# RPI_SmartServo_th_v2.net
KiCad netlist of a schematic drawn in EAGLE
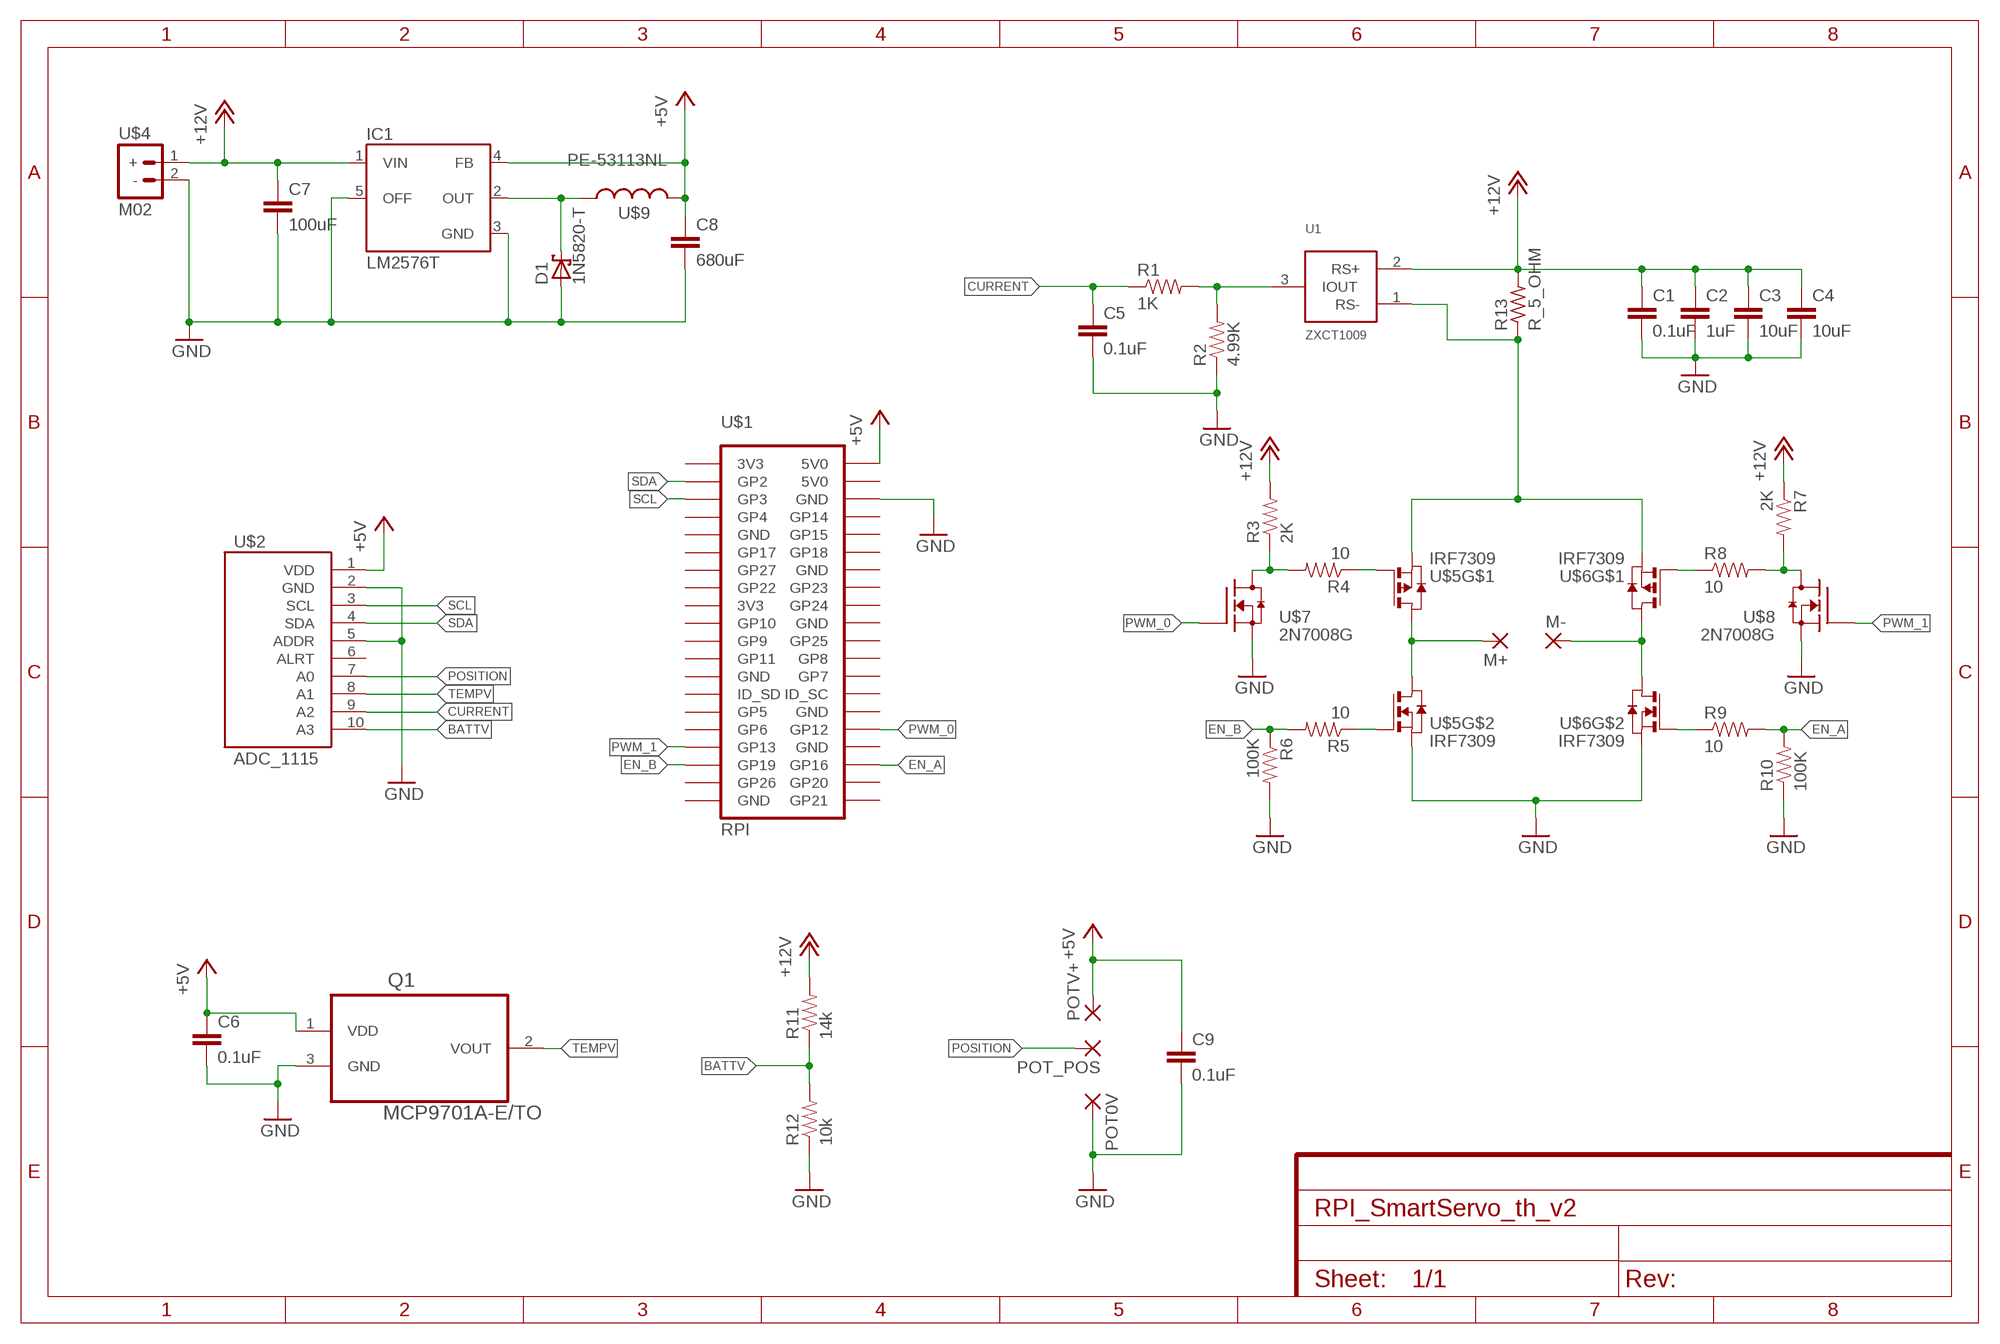
[diagram p0: schematic, sheet 1]

(export (version "E")
  (design (tool "Eeschema 10.0.6"))
  (components
    (comp (ref "C1")
      (value "0.1uF")
      (footprint "eagle-import:C025-025X050")
      (libsource (lib "eagle-import") (part "C-EU025-025X050"))
    )
    (comp (ref "C2")
      (value "1uF")
      (footprint "eagle-import:C025-025X050")
      (libsource (lib "eagle-import") (part "C-EU025-025X050"))
    )
    (comp (ref "C3")
      (value "10uF")
      (footprint "eagle-import:C025-025X050")
      (libsource (lib "eagle-import") (part "C-EU025-025X050"))
    )
    (comp (ref "C4")
      (value "10uF")
      (footprint "eagle-import:C025-025X050")
      (libsource (lib "eagle-import") (part "C-EU025-025X050"))
    )
    (comp (ref "C5")
      (value "0.1uF")
      (footprint "eagle-import:C025-025X050")
      (libsource (lib "eagle-import") (part "C-EU025-025X050"))
    )
    (comp (ref "C6")
      (value "0.1uF")
      (footprint "eagle-import:C025-025X050")
      (libsource (lib "eagle-import") (part "C-EU025-025X050"))
    )
    (comp (ref "C7")
      (value "100uF")
      (footprint "eagle-import:C025-025X050")
      (libsource (lib "eagle-import") (part "C-EU025-025X050"))
    )
    (comp (ref "C8")
      (value "680uF")
      (footprint "eagle-import:C025-025X050")
      (libsource (lib "eagle-import") (part "C-EU025-025X050"))
    )
    (comp (ref "C9")
      (value "0.1uF")
      (footprint "eagle-import:C025-025X050")
      (libsource (lib "eagle-import") (part "C-EU025-025X050"))
    )
    (comp (ref "D1")
      (value "1N5820-T")
      (footprint "eagle-import:C4111-15")
      (libsource (lib "eagle-import") (part "SCHOTTKY-DIODEC4111-15"))
    )
    (comp (ref "IC1")
      (value "LM2576T")
      (footprint "eagle-import:TO220-5")
      (libsource (lib "eagle-import") (part "LM2576T"))
    )
    (comp (ref "M+")
      (value "1,6/0,9")
      (footprint "eagle-import:1,6_0,9")
      (libsource (lib "eagle-import") (part "1,6/0,9"))
    )
    (comp (ref "M-")
      (value "1,6/0,9")
      (footprint "eagle-import:1,6_0,9")
      (libsource (lib "eagle-import") (part "1,6/0,9"))
    )
    (comp (ref "POT0V")
      (value "1,6/0,9")
      (footprint "eagle-import:1,6_0,9")
      (libsource (lib "eagle-import") (part "1,6/0,9"))
    )
    (comp (ref "POTV+")
      (value "1,6/0,9")
      (footprint "eagle-import:1,6_0,9")
      (libsource (lib "eagle-import") (part "1,6/0,9"))
    )
    (comp (ref "POT_POS")
      (value "1,6/0,9")
      (footprint "eagle-import:1,6_0,9")
      (libsource (lib "eagle-import") (part "1,6/0,9"))
    )
    (comp (ref "Q1")
      (value "MCP9701A-E/TO")
      (footprint "eagle-import:TO127P254X533-3")
      (libsource (lib "eagle-import") (part "MCP9701A-E/TO"))
    )
    (comp (ref "R1")
      (value "1K")
      (footprint "eagle-import:AXIAL-0.4")
      (libsource (lib "eagle-import") (part "RESISTORPTH-1/4W"))
    )
    (comp (ref "R2")
      (value "4.99K")
      (footprint "eagle-import:AXIAL-0.4")
      (libsource (lib "eagle-import") (part "RESISTORPTH-1/4W"))
    )
    (comp (ref "R3")
      (value "2K")
      (footprint "eagle-import:AXIAL-0.4")
      (libsource (lib "eagle-import") (part "RESISTORPTH-1/4W"))
    )
    (comp (ref "R4")
      (value "10")
      (footprint "eagle-import:AXIAL-0.4")
      (libsource (lib "eagle-import") (part "RESISTORPTH-1/4W"))
    )
    (comp (ref "R5")
      (value "10")
      (footprint "eagle-import:AXIAL-0.4")
      (libsource (lib "eagle-import") (part "RESISTORPTH-1/4W"))
    )
    (comp (ref "R6")
      (value "100K")
      (footprint "eagle-import:AXIAL-0.4")
      (libsource (lib "eagle-import") (part "RESISTORPTH-1/4W"))
    )
    (comp (ref "R7")
      (value "2K")
      (footprint "eagle-import:AXIAL-0.4")
      (libsource (lib "eagle-import") (part "RESISTORPTH-1/4W"))
    )
    (comp (ref "R8")
      (value "10")
      (footprint "eagle-import:AXIAL-0.4")
      (libsource (lib "eagle-import") (part "RESISTORPTH-1/4W"))
    )
    (comp (ref "R9")
      (value "10")
      (footprint "eagle-import:AXIAL-0.4")
      (libsource (lib "eagle-import") (part "RESISTORPTH-1/4W"))
    )
    (comp (ref "R10")
      (value "100K")
      (footprint "eagle-import:AXIAL-0.4")
      (libsource (lib "eagle-import") (part "RESISTORPTH-1/4W"))
    )
    (comp (ref "R11")
      (value "14k")
      (footprint "eagle-import:AXIAL-0.4")
      (libsource (lib "eagle-import") (part "RESISTORPTH-1/4W"))
    )
    (comp (ref "R12")
      (value "10k")
      (footprint "eagle-import:AXIAL-0.4")
      (libsource (lib "eagle-import") (part "RESISTORPTH-1/4W"))
    )
    (comp (ref "R13")
      (value "R_5_OHM")
      (footprint "eagle-import:0922_22")
      (libsource (lib "eagle-import") (part "R_5_OHM"))
    )
    (comp (ref "U$1")
      (value "RPI")
      (footprint "eagle-import:2X20")
      (libsource (lib "eagle-import") (part "RPI"))
    )
    (comp (ref "U$2")
      (value "ADC_1115")
      (footprint "eagle-import:1X10")
      (libsource (lib "eagle-import") (part "ADC_1115"))
    )
    (comp (ref "U$4")
      (value "M02")
      (footprint "eagle-import:1X02")
      (libsource (lib "eagle-import") (part "M02"))
    )
    (comp (ref "U$5")
      (value "IRF7309")
      (footprint "eagle-import:SO8")
      (libsource (lib "eagle-import") (part "IRF7309"))
    )
    (comp (ref "U$6")
      (value "IRF7309")
      (footprint "eagle-import:SO8")
      (libsource (lib "eagle-import") (part "IRF7309"))
    )
    (comp (ref "U$7")
      (value "2N7008G")
      (footprint "eagle-import:TO-92")
      (libsource (lib "eagle-import") (part "2N7008G"))
    )
    (comp (ref "U$8")
      (value "2N7008G")
      (footprint "eagle-import:TO-92")
      (libsource (lib "eagle-import") (part "2N7008G"))
    )
    (comp (ref "U$9")
      (value "PE-53113NL")
      (footprint "eagle-import:KM-4")
      (libsource (lib "eagle-import") (part "PE-53113NL"))
    )
    (comp (ref "U1")
      (value "ZXCT1009")
      (footprint "eagle-import:SOT23")
      (libsource (lib "eagle-import") (part "ZXCT1009"))
    )
  )
  (nets
    (net (code "1") (name "+5V") (class "Default")
      (node (ref "C6") (pin "1") (pinfunction "1_1") (pintype "passive"))
      (node (ref "C8") (pin "1") (pinfunction "1_1") (pintype "passive"))
      (node (ref "C9") (pin "1") (pinfunction "1_1") (pintype "passive"))
      (node (ref "IC1") (pin "4") (pinfunction "FB_4") (pintype "input"))
      (node (ref "POTV+") (pin "1") (pinfunction "P_1") (pintype "passive"))
      (node (ref "Q1") (pin "1") (pinfunction "VDD_1") (pintype "power_in"))
      (node (ref "U$1") (pin "2") (pinfunction "5V0_2") (pintype "bidirectional"))
      (node (ref "U$2") (pin "1") (pinfunction "VDD_1") (pintype "bidirectional"))
      (node (ref "U$9") (pin "P$2") (pinfunction "2_P$2") (pintype "passive"))
    )
    (net (code "2") (name "+12V") (class "Default")
      (node (ref "C1") (pin "1") (pinfunction "1_1") (pintype "passive"))
      (node (ref "C2") (pin "1") (pinfunction "1_1") (pintype "passive"))
      (node (ref "C3") (pin "1") (pinfunction "1_1") (pintype "passive"))
      (node (ref "C4") (pin "1") (pinfunction "1_1") (pintype "passive"))
      (node (ref "C7") (pin "1") (pinfunction "1_1") (pintype "passive"))
      (node (ref "IC1") (pin "1") (pinfunction "VIN_1") (pintype "power_in"))
      (node (ref "R11") (pin "P$2") (pinfunction "2_P$2") (pintype "passive"))
      (node (ref "R13") (pin "2") (pinfunction "2_2") (pintype "passive"))
      (node (ref "R3") (pin "P$2") (pinfunction "2_P$2") (pintype "passive"))
      (node (ref "R7") (pin "P$1") (pinfunction "1_P$1") (pintype "passive"))
      (node (ref "U$4") (pin "1") (pinfunction "+_1") (pintype "passive"))
      (node (ref "U1") (pin "2") (pinfunction "RS+_2") (pintype "bidirectional"))
    )
    (net (code "3") (name "BATTV") (class "Default")
      (node (ref "R11") (pin "P$1") (pinfunction "1_P$1") (pintype "passive"))
      (node (ref "R12") (pin "P$2") (pinfunction "2_P$2") (pintype "passive"))
      (node (ref "U$2") (pin "10") (pinfunction "A3_10") (pintype "bidirectional"))
    )
    (net (code "4") (name "CURRENT") (class "Default")
      (node (ref "C5") (pin "1") (pinfunction "1_1") (pintype "passive"))
      (node (ref "R1") (pin "P$1") (pinfunction "1_P$1") (pintype "passive"))
      (node (ref "U$2") (pin "9") (pinfunction "A2_9") (pintype "bidirectional"))
    )
    (net (code "5") (name "EN_A") (class "Default")
      (node (ref "R10") (pin "P$2") (pinfunction "2_P$2") (pintype "passive"))
      (node (ref "R9") (pin "P$2") (pinfunction "2_P$2") (pintype "passive"))
      (node (ref "U$1") (pin "36") (pinfunction "GP16_36") (pintype "bidirectional"))
    )
    (net (code "6") (name "EN_B") (class "Default")
      (node (ref "R5") (pin "P$2") (pinfunction "2_P$2") (pintype "passive"))
      (node (ref "R6") (pin "P$1") (pinfunction "1_P$1") (pintype "passive"))
      (node (ref "U$1") (pin "35") (pinfunction "GP19_35") (pintype "bidirectional"))
    )
    (net (code "7") (name "GND") (class "Default")
      (node (ref "C1") (pin "2") (pinfunction "2_2") (pintype "passive"))
      (node (ref "C2") (pin "2") (pinfunction "2_2") (pintype "passive"))
      (node (ref "C3") (pin "2") (pinfunction "2_2") (pintype "passive"))
      (node (ref "C4") (pin "2") (pinfunction "2_2") (pintype "passive"))
      (node (ref "C5") (pin "2") (pinfunction "2_2") (pintype "passive"))
      (node (ref "C6") (pin "2") (pinfunction "2_2") (pintype "passive"))
      (node (ref "C7") (pin "2") (pinfunction "2_2") (pintype "passive"))
      (node (ref "C8") (pin "2") (pinfunction "2_2") (pintype "passive"))
      (node (ref "C9") (pin "2") (pinfunction "2_2") (pintype "passive"))
      (node (ref "D1") (pin "A") (pinfunction "A_A") (pintype "passive"))
      (node (ref "IC1") (pin "3") (pinfunction "GND_3") (pintype "power_in"))
      (node (ref "IC1") (pin "5") (pinfunction "OFF_5") (pintype "input"))
      (node (ref "POT0V") (pin "1") (pinfunction "P_1") (pintype "passive"))
      (node (ref "Q1") (pin "3") (pinfunction "GND_3") (pintype "passive"))
      (node (ref "R10") (pin "P$1") (pinfunction "1_P$1") (pintype "passive"))
      (node (ref "R12") (pin "P$1") (pinfunction "1_P$1") (pintype "passive"))
      (node (ref "R2") (pin "P$1") (pinfunction "1_P$1") (pintype "passive"))
      (node (ref "R6") (pin "P$2") (pinfunction "2_P$2") (pintype "passive"))
      (node (ref "U$1") (pin "6") (pinfunction "GND_6") (pintype "bidirectional"))
      (node (ref "U$2") (pin "2") (pinfunction "GND_2") (pintype "bidirectional"))
      (node (ref "U$2") (pin "5") (pinfunction "ADDR_5") (pintype "bidirectional"))
      (node (ref "U$4") (pin "2") (pinfunction "-_2") (pintype "passive"))
      (node (ref "U$5") (pin "1") (pinfunction "S_1") (pintype "passive"))
      (node (ref "U$6") (pin "1") (pinfunction "S_1") (pintype "passive"))
      (node (ref "U$7") (pin "1") (pinfunction "S_1") (pintype "passive"))
      (node (ref "U$8") (pin "1") (pinfunction "S_1") (pintype "passive"))
    )
    (net (code "8") (name "Net-(IC1-OUT)") (class "Default")
      (node (ref "D1") (pin "C") (pinfunction "C_C") (pintype "passive"))
      (node (ref "IC1") (pin "2") (pinfunction "OUT_2") (pintype "output"))
      (node (ref "U$9") (pin "P$1") (pinfunction "1_P$1") (pintype "passive"))
    )
    (net (code "9") (name "Net-(M+-P)") (class "Default")
      (node (ref "M+") (pin "1") (pinfunction "P_1") (pintype "passive"))
      (node (ref "U$5") (pin "5") (pinfunction "D_5") (pintype "passive"))
      (node (ref "U$5") (pin "6") (pinfunction "D_6") (pintype "passive"))
      (node (ref "U$5") (pin "7") (pinfunction "D_7") (pintype "passive"))
      (node (ref "U$5") (pin "8") (pinfunction "D_8") (pintype "passive"))
    )
    (net (code "10") (name "Net-(M--P)") (class "Default")
      (node (ref "M-") (pin "1") (pinfunction "P_1") (pintype "passive"))
      (node (ref "U$6") (pin "5") (pinfunction "D_5") (pintype "passive"))
      (node (ref "U$6") (pin "6") (pinfunction "D_6") (pintype "passive"))
      (node (ref "U$6") (pin "7") (pinfunction "D_7") (pintype "passive"))
      (node (ref "U$6") (pin "8") (pinfunction "D_8") (pintype "passive"))
    )
    (net (code "11") (name "Net-(R1-2)") (class "Default")
      (node (ref "R1") (pin "P$2") (pinfunction "2_P$2") (pintype "passive"))
      (node (ref "R2") (pin "P$2") (pinfunction "2_P$2") (pintype "passive"))
      (node (ref "U1") (pin "3") (pinfunction "IOUT_3") (pintype "bidirectional"))
    )
    (net (code "12") (name "Net-(R3-1)") (class "Default")
      (node (ref "R3") (pin "P$1") (pinfunction "1_P$1") (pintype "passive"))
      (node (ref "R4") (pin "P$2") (pinfunction "2_P$2") (pintype "passive"))
      (node (ref "U$7") (pin "3") (pinfunction "D_3") (pintype "passive"))
    )
    (net (code "13") (name "Net-(R4-1)") (class "Default")
      (node (ref "R4") (pin "P$1") (pinfunction "1_P$1") (pintype "passive"))
      (node (ref "U$5") (pin "4") (pinfunction "G_4") (pintype "passive"))
    )
    (net (code "14") (name "Net-(R5-1)") (class "Default")
      (node (ref "R5") (pin "P$1") (pinfunction "1_P$1") (pintype "passive"))
      (node (ref "U$5") (pin "2") (pinfunction "G_2") (pintype "passive"))
    )
    (net (code "15") (name "Net-(R7-2)") (class "Default")
      (node (ref "R7") (pin "P$2") (pinfunction "2_P$2") (pintype "passive"))
      (node (ref "R8") (pin "P$2") (pinfunction "2_P$2") (pintype "passive"))
      (node (ref "U$8") (pin "3") (pinfunction "D_3") (pintype "passive"))
    )
    (net (code "16") (name "Net-(R8-1)") (class "Default")
      (node (ref "R8") (pin "P$1") (pinfunction "1_P$1") (pintype "passive"))
      (node (ref "U$6") (pin "4") (pinfunction "G_4") (pintype "passive"))
    )
    (net (code "17") (name "Net-(R9-1)") (class "Default")
      (node (ref "R9") (pin "P$1") (pinfunction "1_P$1") (pintype "passive"))
      (node (ref "U$6") (pin "2") (pinfunction "G_2") (pintype "passive"))
    )
    (net (code "18") (name "Net-(U$5A-S)") (class "Default")
      (node (ref "R13") (pin "1") (pinfunction "1_1") (pintype "passive"))
      (node (ref "U$5") (pin "3") (pinfunction "S_3") (pintype "passive"))
      (node (ref "U$6") (pin "3") (pinfunction "S_3") (pintype "passive"))
      (node (ref "U1") (pin "1") (pinfunction "RS-_1") (pintype "bidirectional"))
    )
    (net (code "19") (name "POSITION") (class "Default")
      (node (ref "POT_POS") (pin "1") (pinfunction "P_1") (pintype "passive"))
      (node (ref "U$2") (pin "7") (pinfunction "A0_7") (pintype "bidirectional"))
    )
    (net (code "20") (name "PWM_0") (class "Default")
      (node (ref "U$1") (pin "32") (pinfunction "GP12_32") (pintype "bidirectional"))
      (node (ref "U$7") (pin "2") (pinfunction "G_2") (pintype "passive"))
    )
    (net (code "21") (name "PWM_1") (class "Default")
      (node (ref "U$1") (pin "33") (pinfunction "GP13_33") (pintype "bidirectional"))
      (node (ref "U$8") (pin "2") (pinfunction "G_2") (pintype "passive"))
    )
    (net (code "22") (name "SCL") (class "Default")
      (node (ref "U$1") (pin "5") (pinfunction "GP3_5") (pintype "bidirectional"))
      (node (ref "U$2") (pin "3") (pinfunction "SCL_3") (pintype "bidirectional"))
    )
    (net (code "23") (name "SDA") (class "Default")
      (node (ref "U$1") (pin "3") (pinfunction "GP2_3") (pintype "bidirectional"))
      (node (ref "U$2") (pin "4") (pinfunction "SDA_4") (pintype "bidirectional"))
    )
    (net (code "24") (name "TEMPV") (class "Default")
      (node (ref "Q1") (pin "2") (pinfunction "VOUT_2") (pintype "output"))
      (node (ref "U$2") (pin "8") (pinfunction "A1_8") (pintype "bidirectional"))
    )
    (net (code "25") (name "unconnected-(U$1-3V3-Pad1)") (class "Default")
      (node (ref "U$1") (pin "1") (pinfunction "3V3_1") (pintype "bidirectional"))
    )
    (net (code "26") (name "unconnected-(U$1-3V3-Pad17)") (class "Default")
      (node (ref "U$1") (pin "17") (pinfunction "3V3_17") (pintype "bidirectional"))
    )
    (net (code "27") (name "unconnected-(U$1-5V0-Pad4)") (class "Default")
      (node (ref "U$1") (pin "4") (pinfunction "5V0_4") (pintype "bidirectional"))
    )
    (net (code "28") (name "unconnected-(U$1-GND-Pad9)") (class "Default")
      (node (ref "U$1") (pin "9") (pinfunction "GND_9") (pintype "bidirectional"))
    )
    (net (code "29") (name "unconnected-(U$1-GND-Pad14)") (class "Default")
      (node (ref "U$1") (pin "14") (pinfunction "GND_14") (pintype "bidirectional"))
    )
    (net (code "30") (name "unconnected-(U$1-GND-Pad20)") (class "Default")
      (node (ref "U$1") (pin "20") (pinfunction "GND_20") (pintype "bidirectional"))
    )
    (net (code "31") (name "unconnected-(U$1-GND-Pad25)") (class "Default")
      (node (ref "U$1") (pin "25") (pinfunction "GND_25") (pintype "bidirectional"))
    )
    (net (code "32") (name "unconnected-(U$1-GND-Pad30)") (class "Default")
      (node (ref "U$1") (pin "30") (pinfunction "GND_30") (pintype "bidirectional"))
    )
    (net (code "33") (name "unconnected-(U$1-GND-Pad34)") (class "Default")
      (node (ref "U$1") (pin "34") (pinfunction "GND_34") (pintype "bidirectional"))
    )
    (net (code "34") (name "unconnected-(U$1-GND-Pad39)") (class "Default")
      (node (ref "U$1") (pin "39") (pinfunction "GND_39") (pintype "bidirectional"))
    )
    (net (code "35") (name "unconnected-(U$1-GP4-Pad7)") (class "Default")
      (node (ref "U$1") (pin "7") (pinfunction "GP4_7") (pintype "bidirectional"))
    )
    (net (code "36") (name "unconnected-(U$1-GP5-Pad29)") (class "Default")
      (node (ref "U$1") (pin "29") (pinfunction "GP5_29") (pintype "bidirectional"))
    )
    (net (code "37") (name "unconnected-(U$1-GP6-Pad31)") (class "Default")
      (node (ref "U$1") (pin "31") (pinfunction "GP6_31") (pintype "bidirectional"))
    )
    (net (code "38") (name "unconnected-(U$1-GP7-Pad26)") (class "Default")
      (node (ref "U$1") (pin "26") (pinfunction "GP7_26") (pintype "bidirectional"))
    )
    (net (code "39") (name "unconnected-(U$1-GP8-Pad24)") (class "Default")
      (node (ref "U$1") (pin "24") (pinfunction "GP8_24") (pintype "bidirectional"))
    )
    (net (code "40") (name "unconnected-(U$1-GP9-Pad21)") (class "Default")
      (node (ref "U$1") (pin "21") (pinfunction "GP9_21") (pintype "bidirectional"))
    )
    (net (code "41") (name "unconnected-(U$1-GP10-Pad19)") (class "Default")
      (node (ref "U$1") (pin "19") (pinfunction "GP10_19") (pintype "bidirectional"))
    )
    (net (code "42") (name "unconnected-(U$1-GP11-Pad23)") (class "Default")
      (node (ref "U$1") (pin "23") (pinfunction "GP11_23") (pintype "bidirectional"))
    )
    (net (code "43") (name "unconnected-(U$1-GP14-Pad8)") (class "Default")
      (node (ref "U$1") (pin "8") (pinfunction "GP14_8") (pintype "bidirectional"))
    )
    (net (code "44") (name "unconnected-(U$1-GP15-Pad10)") (class "Default")
      (node (ref "U$1") (pin "10") (pinfunction "GP15_10") (pintype "bidirectional"))
    )
    (net (code "45") (name "unconnected-(U$1-GP17-Pad11)") (class "Default")
      (node (ref "U$1") (pin "11") (pinfunction "GP17_11") (pintype "bidirectional"))
    )
    (net (code "46") (name "unconnected-(U$1-GP18-Pad12)") (class "Default")
      (node (ref "U$1") (pin "12") (pinfunction "GP18_12") (pintype "bidirectional"))
    )
    (net (code "47") (name "unconnected-(U$1-GP20-Pad38)") (class "Default")
      (node (ref "U$1") (pin "38") (pinfunction "GP20_38") (pintype "bidirectional"))
    )
    (net (code "48") (name "unconnected-(U$1-GP21-Pad40)") (class "Default")
      (node (ref "U$1") (pin "40") (pinfunction "GP21_40") (pintype "bidirectional"))
    )
    (net (code "49") (name "unconnected-(U$1-GP22-Pad15)") (class "Default")
      (node (ref "U$1") (pin "15") (pinfunction "GP22_15") (pintype "bidirectional"))
    )
    (net (code "50") (name "unconnected-(U$1-GP23-Pad16)") (class "Default")
      (node (ref "U$1") (pin "16") (pinfunction "GP23_16") (pintype "bidirectional"))
    )
    (net (code "51") (name "unconnected-(U$1-GP24-Pad18)") (class "Default")
      (node (ref "U$1") (pin "18") (pinfunction "GP24_18") (pintype "bidirectional"))
    )
    (net (code "52") (name "unconnected-(U$1-GP25-Pad22)") (class "Default")
      (node (ref "U$1") (pin "22") (pinfunction "GP25_22") (pintype "bidirectional"))
    )
    (net (code "53") (name "unconnected-(U$1-GP26-Pad37)") (class "Default")
      (node (ref "U$1") (pin "37") (pinfunction "GP26_37") (pintype "bidirectional"))
    )
    (net (code "54") (name "unconnected-(U$1-GP27-Pad13)") (class "Default")
      (node (ref "U$1") (pin "13") (pinfunction "GP27_13") (pintype "bidirectional"))
    )
    (net (code "55") (name "unconnected-(U$1-ID_SC-Pad28)") (class "Default")
      (node (ref "U$1") (pin "28") (pinfunction "ID_SC_28") (pintype "bidirectional"))
    )
    (net (code "56") (name "unconnected-(U$1-ID_SD-Pad27)") (class "Default")
      (node (ref "U$1") (pin "27") (pinfunction "ID_SD_27") (pintype "bidirectional"))
    )
    (net (code "57") (name "unconnected-(U$2-ALRT-Pad6)") (class "Default")
      (node (ref "U$2") (pin "6") (pinfunction "ALRT_6") (pintype "bidirectional"))
    )
  )
)
